# FilterControl_Schematic.net
KiCad netlist of a schematic drawn in Altium Designer
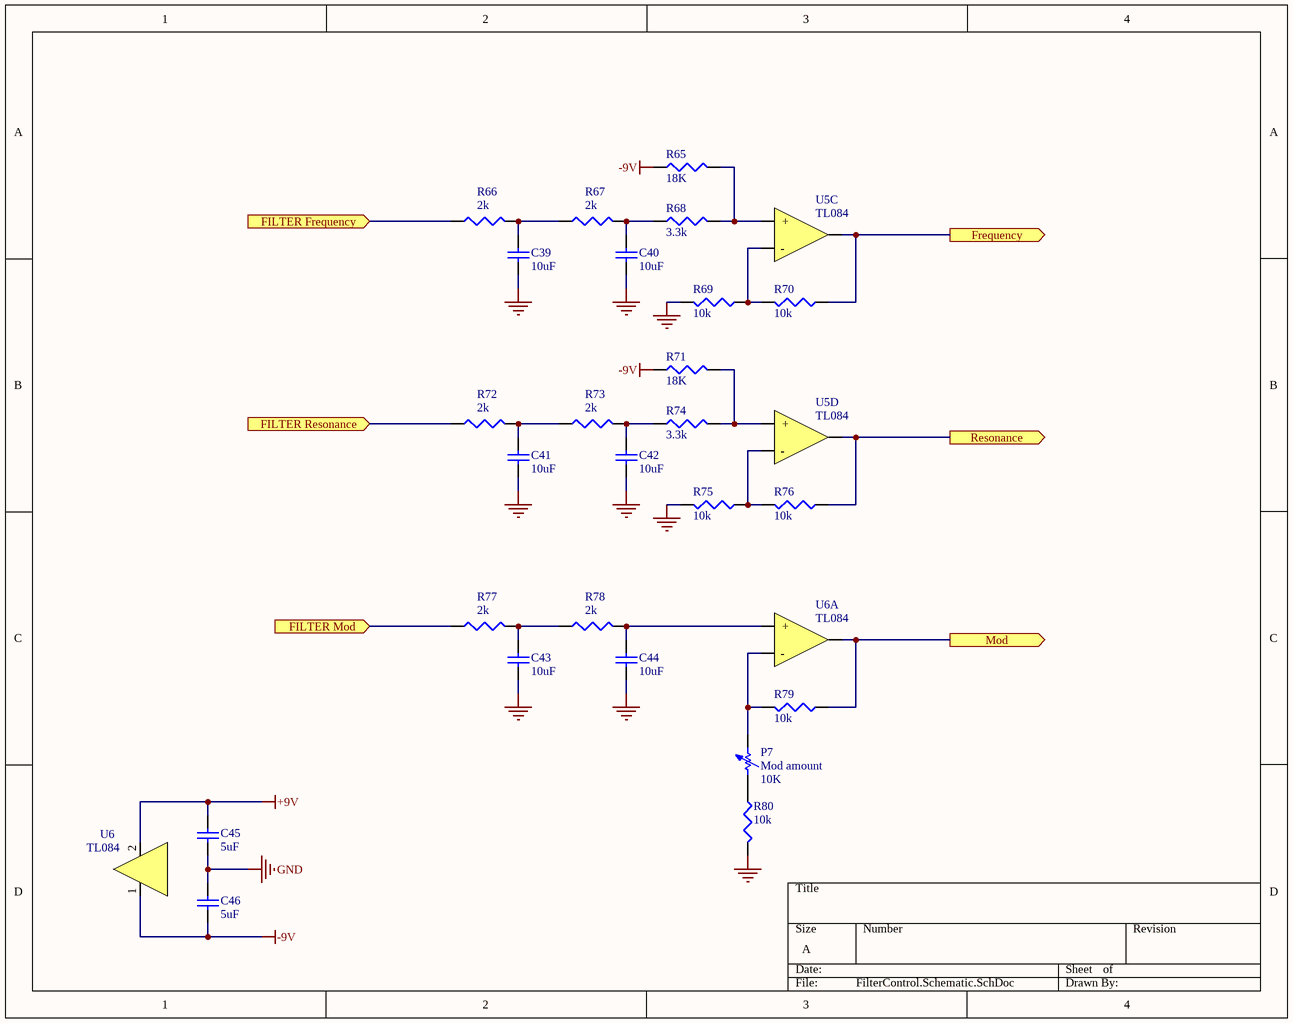
[diagram p0: FilterControl.Schematic.SchDoc]

(export (version "E")
  (design (tool "Eeschema 10.0.6"))
  (components
    (comp (ref "C39")
      (value "10uF")
      (footprint "CAPC1608N")
      (description "Capacitor (Semiconductor SIM Model)")
      (fields (field (name "PUBLISHER") "Altium Limited"))
      (libsource (lib "Miscellaneous Devices") (part "Cap Semi"))
    )
    (comp (ref "C40")
      (value "10uF")
      (footprint "CAPC1608N")
      (description "Capacitor (Semiconductor SIM Model)")
      (fields (field (name "PUBLISHER") "Altium Limited"))
      (libsource (lib "Miscellaneous Devices") (part "Cap Semi"))
    )
    (comp (ref "C41")
      (value "10uF")
      (footprint "CAPC1608N")
      (description "Capacitor (Semiconductor SIM Model)")
      (fields (field (name "PUBLISHER") "Altium Limited"))
      (libsource (lib "Miscellaneous Devices") (part "Cap Semi"))
    )
    (comp (ref "C42")
      (value "10uF")
      (footprint "CAPC1608N")
      (description "Capacitor (Semiconductor SIM Model)")
      (fields (field (name "PUBLISHER") "Altium Limited"))
      (libsource (lib "Miscellaneous Devices") (part "Cap Semi"))
    )
    (comp (ref "C43")
      (value "10uF")
      (footprint "CAPC1608N")
      (description "Capacitor (Semiconductor SIM Model)")
      (fields (field (name "PUBLISHER") "Altium Limited"))
      (libsource (lib "Miscellaneous Devices") (part "Cap Semi"))
    )
    (comp (ref "C44")
      (value "10uF")
      (footprint "CAPC1608N")
      (description "Capacitor (Semiconductor SIM Model)")
      (fields (field (name "PUBLISHER") "Altium Limited"))
      (libsource (lib "Miscellaneous Devices") (part "Cap Semi"))
    )
    (comp (ref "C45")
      (value "5uF")
      (footprint "CAPC1608N")
      (description "Capacitor (Semiconductor SIM Model)")
      (fields (field (name "PUBLISHER") "Altium Limited"))
      (libsource (lib "Miscellaneous Devices") (part "Cap Semi"))
    )
    (comp (ref "C46")
      (value "5uF")
      (footprint "CAPC1608N")
      (description "Capacitor (Semiconductor SIM Model)")
      (fields (field (name "PUBLISHER") "Altium Limited"))
      (libsource (lib "Miscellaneous Devices") (part "Cap Semi"))
    )
    (comp (ref "P7")
      (value "Mod amount")
      (footprint "CAPC1608N")
      (description "Variable Resistor")
      (fields (field (name "ALTIUM_VALUE") "10K") (field (name "PUBLISHER") "Altium Limited"))
      (libsource (lib "Miscellaneous Devices") (part "Res Adj1"))
    )
    (comp (ref "R65")
      (value "18K")
      (footprint "CAPC1608N")
      (description "Resistor")
      (fields (field (name "PUBLISHER") "Altium Limited"))
      (libsource (lib "Miscellaneous Devices") (part "Res3"))
    )
    (comp (ref "R66")
      (value "2k")
      (footprint "CAPC1608N")
      (description "Resistor")
      (fields (field (name "PUBLISHER") "Altium Limited"))
      (libsource (lib "Miscellaneous Devices") (part "Res3"))
    )
    (comp (ref "R67")
      (value "2k")
      (footprint "CAPC1608N")
      (description "Resistor")
      (fields (field (name "PUBLISHER") "Altium Limited"))
      (libsource (lib "Miscellaneous Devices") (part "Res3"))
    )
    (comp (ref "R68")
      (value "3.3k")
      (footprint "CAPC1608N")
      (description "Resistor")
      (fields (field (name "PUBLISHER") "Altium Limited"))
      (libsource (lib "Miscellaneous Devices") (part "Res3"))
    )
    (comp (ref "R69")
      (value "10k")
      (footprint "CAPC1608N")
      (description "Resistor")
      (fields (field (name "PUBLISHER") "Altium Limited"))
      (libsource (lib "Miscellaneous Devices") (part "Res3"))
    )
    (comp (ref "R70")
      (value "10k")
      (footprint "CAPC1608N")
      (description "Resistor")
      (fields (field (name "PUBLISHER") "Altium Limited"))
      (libsource (lib "Miscellaneous Devices") (part "Res3"))
    )
    (comp (ref "R71")
      (value "18K")
      (footprint "CAPC1608N")
      (description "Resistor")
      (fields (field (name "PUBLISHER") "Altium Limited"))
      (libsource (lib "Miscellaneous Devices") (part "Res3"))
    )
    (comp (ref "R72")
      (value "2k")
      (footprint "CAPC1608N")
      (description "Resistor")
      (fields (field (name "PUBLISHER") "Altium Limited"))
      (libsource (lib "Miscellaneous Devices") (part "Res3"))
    )
    (comp (ref "R73")
      (value "2k")
      (footprint "CAPC1608N")
      (description "Resistor")
      (fields (field (name "PUBLISHER") "Altium Limited"))
      (libsource (lib "Miscellaneous Devices") (part "Res3"))
    )
    (comp (ref "R74")
      (value "3.3k")
      (footprint "CAPC1608N")
      (description "Resistor")
      (fields (field (name "PUBLISHER") "Altium Limited"))
      (libsource (lib "Miscellaneous Devices") (part "Res3"))
    )
    (comp (ref "R75")
      (value "10k")
      (footprint "CAPC1608N")
      (description "Resistor")
      (fields (field (name "PUBLISHER") "Altium Limited"))
      (libsource (lib "Miscellaneous Devices") (part "Res3"))
    )
    (comp (ref "R76")
      (value "10k")
      (footprint "CAPC1608N")
      (description "Resistor")
      (fields (field (name "PUBLISHER") "Altium Limited"))
      (libsource (lib "Miscellaneous Devices") (part "Res3"))
    )
    (comp (ref "R77")
      (value "2k")
      (footprint "CAPC1608N")
      (description "Resistor")
      (fields (field (name "PUBLISHER") "Altium Limited"))
      (libsource (lib "Miscellaneous Devices") (part "Res3"))
    )
    (comp (ref "R78")
      (value "2k")
      (footprint "CAPC1608N")
      (description "Resistor")
      (fields (field (name "PUBLISHER") "Altium Limited"))
      (libsource (lib "Miscellaneous Devices") (part "Res3"))
    )
    (comp (ref "R79")
      (value "10k")
      (footprint "CAPC1608N")
      (description "Resistor")
      (fields (field (name "PUBLISHER") "Altium Limited"))
      (libsource (lib "Miscellaneous Devices") (part "Res3"))
    )
    (comp (ref "R80")
      (value "10k")
      (footprint "CAPC1608N")
      (description "Resistor")
      (fields (field (name "PUBLISHER") "Altium Limited"))
      (libsource (lib "Miscellaneous Devices") (part "Res3"))
    )
    (comp (ref "U5C")
      (value "TL084")
      (footprint "TL084 - 3pads")
      (libsource (lib "SynthyTwo.Components") (part "TL084"))
    )
    (comp (ref "U5D")
      (value "TL084")
      (footprint "TL084 - 3pads")
      (libsource (lib "SynthyTwo.Components") (part "TL084"))
    )
    (comp (ref "U6")
      (value "TL084")
      (footprint "TL084 - Alim")
      (libsource (lib "SynthyTwo.Components") (part "TL_CLEAN"))
    )
    (comp (ref "U6A")
      (value "TL084")
      (footprint "TL084 - 3pads")
      (libsource (lib "SynthyTwo.Components") (part "TL084"))
    )
  )
  (nets
    (net (code "1") (name "+9V") (class "Default")
      (node (ref "C45") (pin "1") (pinfunction "1_1") (pintype "passive"))
      (node (ref "U6") (pin "2") (pinfunction "VCC-_2") (pintype "passive"))
    )
    (net (code "2") (name "-9V") (class "Default")
      (node (ref "C46") (pin "2") (pinfunction "2_2") (pintype "passive"))
      (node (ref "R65") (pin "1") (pinfunction "1_1") (pintype "passive"))
      (node (ref "R71") (pin "1") (pinfunction "1_1") (pintype "passive"))
      (node (ref "U6") (pin "1") (pinfunction "VCC+_1") (pintype "passive"))
    )
    (net (code "3") (name "/FILTER Frequency") (class "Default")
      (node (ref "R66") (pin "1") (pinfunction "1_1") (pintype "passive"))
    )
    (net (code "4") (name "/FILTER Mod") (class "Default")
      (node (ref "R77") (pin "1") (pinfunction "1_1") (pintype "passive"))
    )
    (net (code "5") (name "/FILTER Resonance") (class "Default")
      (node (ref "R72") (pin "1") (pinfunction "1_1") (pintype "passive"))
    )
    (net (code "6") (name "/Frequency") (class "Default")
      (node (ref "R70") (pin "1") (pinfunction "1_1") (pintype "passive"))
      (node (ref "U5C") (pin "1") (pinfunction "OUT_1") (pintype "passive"))
    )
    (net (code "7") (name "/Mod") (class "Default")
      (node (ref "R79") (pin "1") (pinfunction "1_1") (pintype "passive"))
      (node (ref "U6A") (pin "1") (pinfunction "OUT_1") (pintype "passive"))
    )
    (net (code "8") (name "/Resonance") (class "Default")
      (node (ref "R76") (pin "1") (pinfunction "1_1") (pintype "passive"))
      (node (ref "U5D") (pin "1") (pinfunction "OUT_1") (pintype "passive"))
    )
    (net (code "9") (name "GND") (class "Default")
      (node (ref "C39") (pin "1") (pinfunction "1_1") (pintype "passive"))
      (node (ref "C40") (pin "1") (pinfunction "1_1") (pintype "passive"))
      (node (ref "C41") (pin "1") (pinfunction "1_1") (pintype "passive"))
      (node (ref "C42") (pin "1") (pinfunction "1_1") (pintype "passive"))
      (node (ref "C43") (pin "1") (pinfunction "1_1") (pintype "passive"))
      (node (ref "C44") (pin "1") (pinfunction "1_1") (pintype "passive"))
      (node (ref "C45") (pin "2") (pinfunction "2_2") (pintype "passive"))
      (node (ref "C46") (pin "1") (pinfunction "1_1") (pintype "passive"))
      (node (ref "R69") (pin "2") (pinfunction "2_2") (pintype "passive"))
      (node (ref "R75") (pin "2") (pinfunction "2_2") (pintype "passive"))
      (node (ref "R80") (pin "2") (pinfunction "2_2") (pintype "passive"))
    )
    (net (code "10") (name "Net-(C39-Pad2)") (class "Default")
      (node (ref "C39") (pin "2") (pinfunction "2_2") (pintype "passive"))
      (node (ref "R66") (pin "2") (pinfunction "2_2") (pintype "passive"))
      (node (ref "R67") (pin "1") (pinfunction "1_1") (pintype "passive"))
    )
    (net (code "11") (name "Net-(C40-Pad2)") (class "Default")
      (node (ref "C40") (pin "2") (pinfunction "2_2") (pintype "passive"))
      (node (ref "R67") (pin "2") (pinfunction "2_2") (pintype "passive"))
      (node (ref "R68") (pin "1") (pinfunction "1_1") (pintype "passive"))
    )
    (net (code "12") (name "Net-(C41-Pad2)") (class "Default")
      (node (ref "C41") (pin "2") (pinfunction "2_2") (pintype "passive"))
      (node (ref "R72") (pin "2") (pinfunction "2_2") (pintype "passive"))
      (node (ref "R73") (pin "1") (pinfunction "1_1") (pintype "passive"))
    )
    (net (code "13") (name "Net-(C42-Pad2)") (class "Default")
      (node (ref "C42") (pin "2") (pinfunction "2_2") (pintype "passive"))
      (node (ref "R73") (pin "2") (pinfunction "2_2") (pintype "passive"))
      (node (ref "R74") (pin "1") (pinfunction "1_1") (pintype "passive"))
    )
    (net (code "14") (name "Net-(C43-Pad2)") (class "Default")
      (node (ref "C43") (pin "2") (pinfunction "2_2") (pintype "passive"))
      (node (ref "R77") (pin "2") (pinfunction "2_2") (pintype "passive"))
      (node (ref "R78") (pin "1") (pinfunction "1_1") (pintype "passive"))
    )
    (net (code "15") (name "Net-(P7-Pad1)") (class "Default")
      (node (ref "P7") (pin "1") (pinfunction "1_1") (pintype "passive"))
      (node (ref "R80") (pin "1") (pinfunction "1_1") (pintype "passive"))
    )
    (net (code "16") (name "Net-(U5C-+)") (class "Default")
      (node (ref "R65") (pin "2") (pinfunction "2_2") (pintype "passive"))
      (node (ref "R68") (pin "2") (pinfunction "2_2") (pintype "passive"))
      (node (ref "U5C") (pin "3") (pinfunction "+_3") (pintype "passive"))
    )
    (net (code "17") (name "Net-(U5C--)") (class "Default")
      (node (ref "R69") (pin "1") (pinfunction "1_1") (pintype "passive"))
      (node (ref "R70") (pin "2") (pinfunction "2_2") (pintype "passive"))
      (node (ref "U5C") (pin "2") (pinfunction "-_2") (pintype "passive"))
    )
    (net (code "18") (name "Net-(U5D-+)") (class "Default")
      (node (ref "R71") (pin "2") (pinfunction "2_2") (pintype "passive"))
      (node (ref "R74") (pin "2") (pinfunction "2_2") (pintype "passive"))
      (node (ref "U5D") (pin "3") (pinfunction "+_3") (pintype "passive"))
    )
    (net (code "19") (name "Net-(U5D--)") (class "Default")
      (node (ref "R75") (pin "1") (pinfunction "1_1") (pintype "passive"))
      (node (ref "R76") (pin "2") (pinfunction "2_2") (pintype "passive"))
      (node (ref "U5D") (pin "2") (pinfunction "-_2") (pintype "passive"))
    )
    (net (code "20") (name "Net-(U6A-+)") (class "Default")
      (node (ref "C44") (pin "2") (pinfunction "2_2") (pintype "passive"))
      (node (ref "R78") (pin "2") (pinfunction "2_2") (pintype "passive"))
      (node (ref "U6A") (pin "3") (pinfunction "+_3") (pintype "passive"))
    )
    (net (code "21") (name "Net-(U6A--)") (class "Default")
      (node (ref "P7") (pin "2") (pinfunction "2_2") (pintype "passive"))
      (node (ref "R79") (pin "2") (pinfunction "2_2") (pintype "passive"))
      (node (ref "U6A") (pin "2") (pinfunction "-_2") (pintype "passive"))
    )
  )
)
